# Page2.net
KiCad netlist of a schematic drawn in Altium Designer
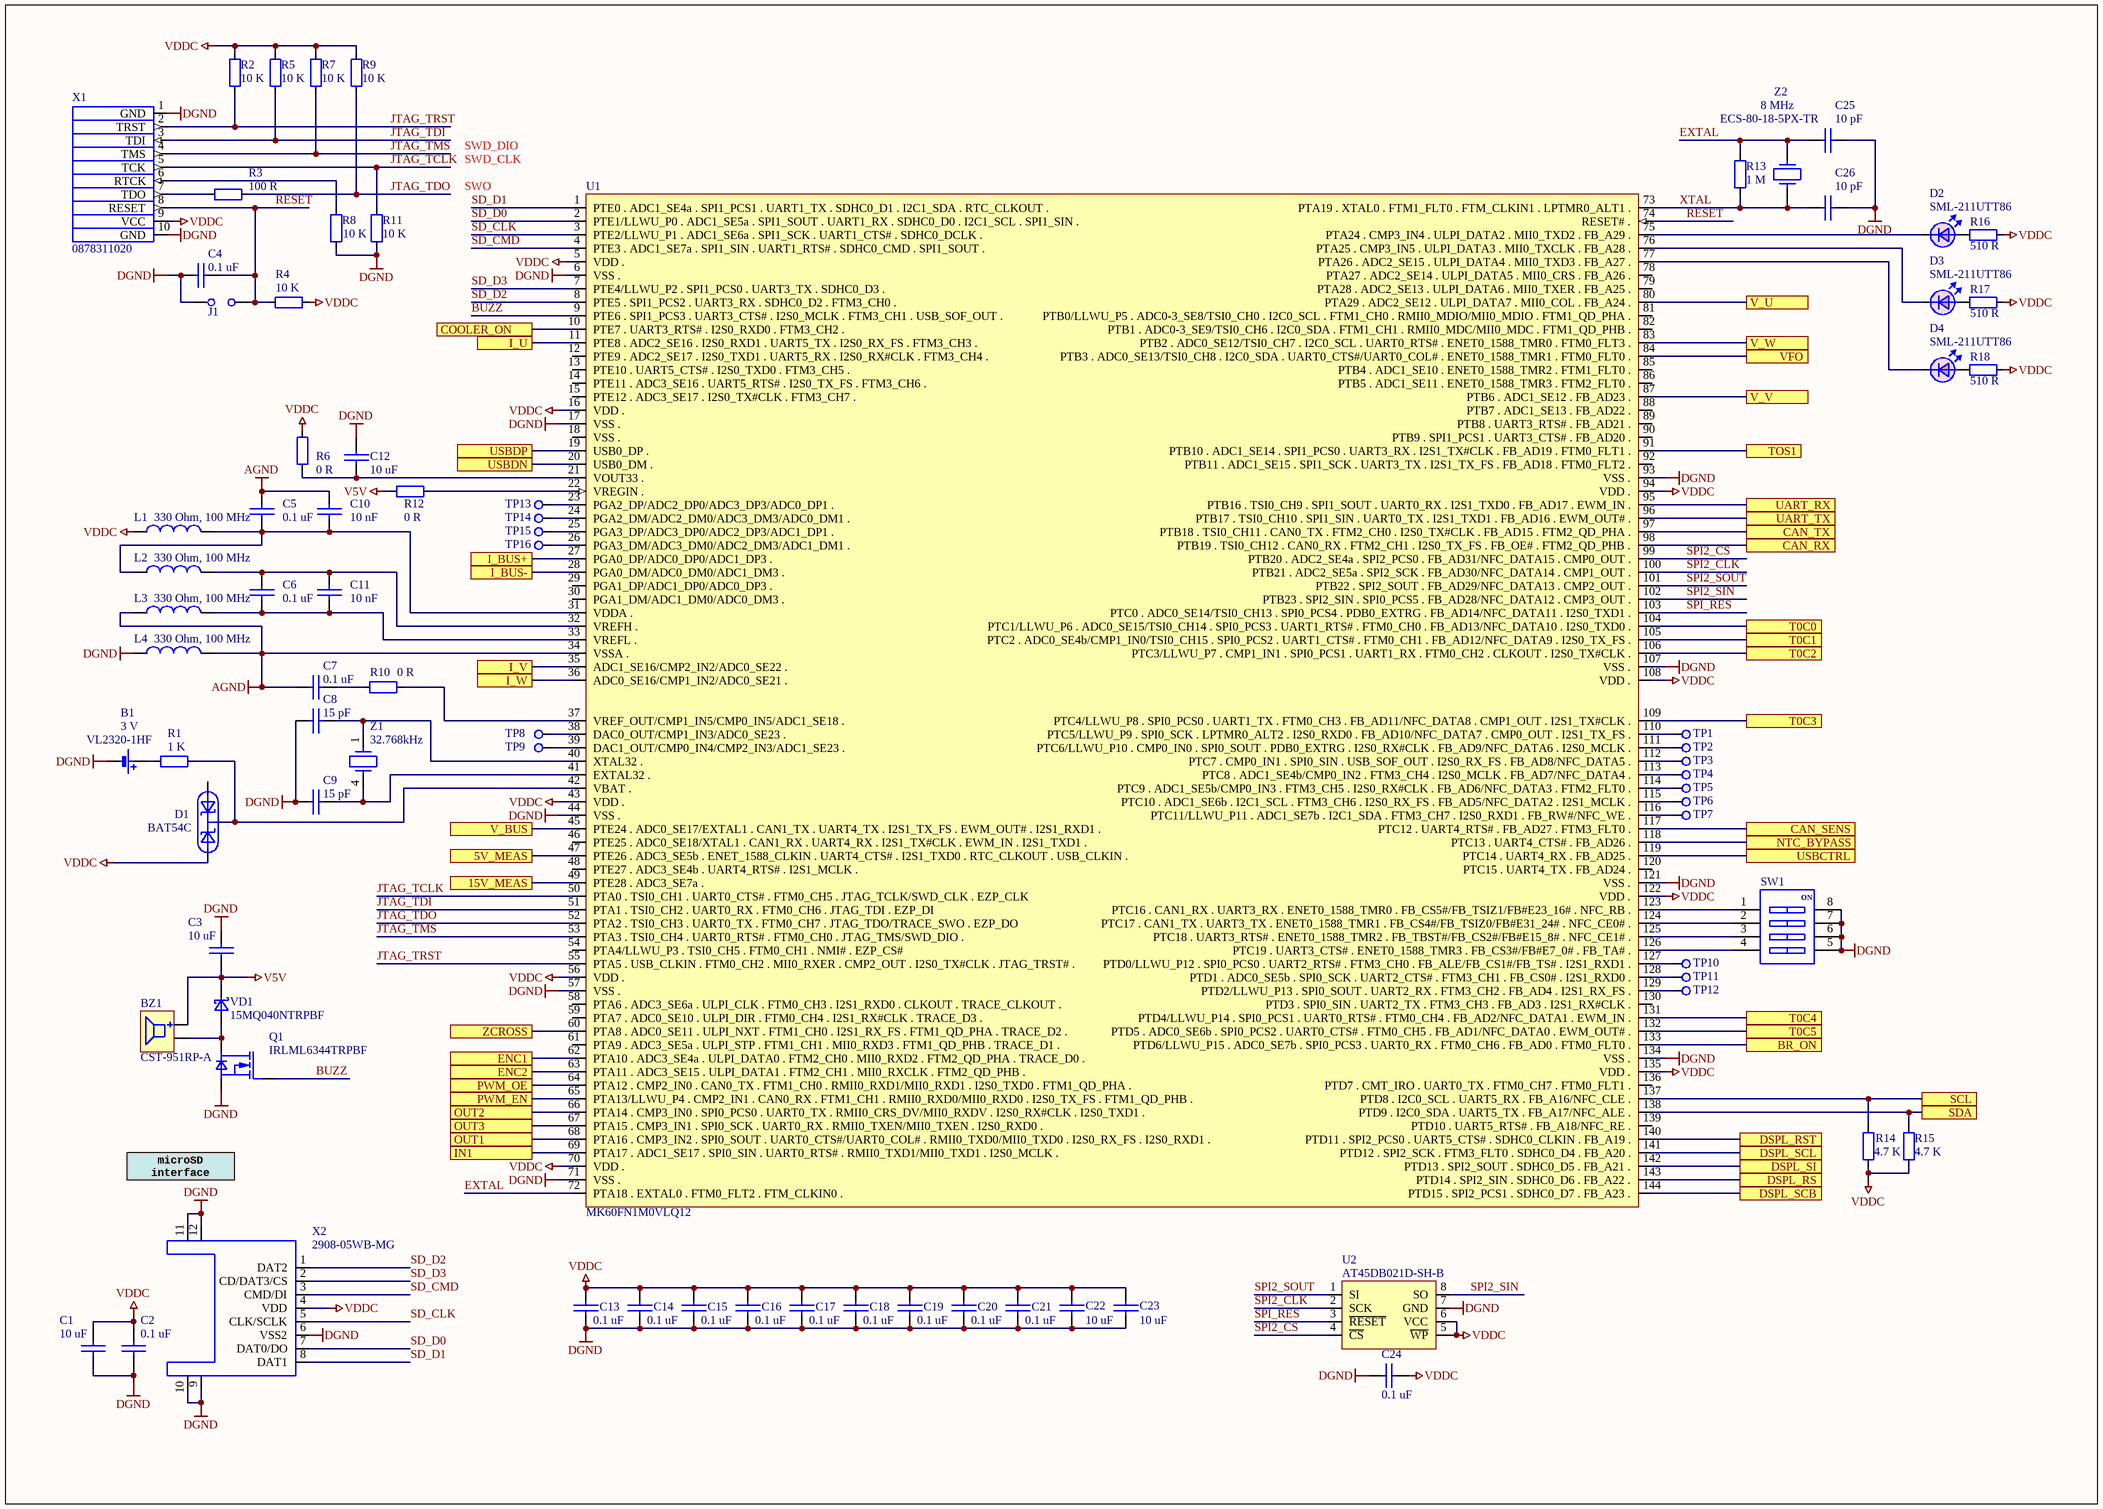
[diagram p0: Page2.SchDoc]

(export (version "E")
  (design (tool "Eeschema 10.0.6"))
  (components
    (comp (ref "B1")
      (value "VL2320-1HF")
      (footprint "SANYO ML2430")
      (description "Rechargeable Litium battery, Sanyo, 100 mAh, 3.1 V")
      (fields
        (field (name "PARTNUM") "P083-ND")
        (field (name "MANUFACTURER") "Panasonic - BSG")
        (field (name "ALTIUM_VALUE") "3 V")
      )
      (libsource (lib "*") (part "VL2320-1HF"))
    )
    (comp (ref "BZ1")
      (value "CST-951RP-A")
      (footprint "CST-951RP-A")
      (description "Buzzer CST-951AP, 4,5...5,5 V,  85 dB,   80 mA")
      (fields (field (name "MANUFACTURER") "CUI Inc") (field (name "PARTNUM") "102-1462-ND"))
      (libsource (lib "ea_Sound_devices") (part "CST-951RP-A"))
    )
    (comp (ref "C1")
      (value "10 uF")
      (footprint "2012[0805]")
      (description "10 uF, 16V, X5R, ±10%, 0805")
      (fields (field (name "MANUFACTURER") "TDK Corporation") (field (name "TOLERANCE") "±10%"))
      (libsource (lib "ea_Capacitors") (part "C2012X5R1C106K/0.85"))
    )
    (comp (ref "C2")
      (value "0.1 uF")
      (footprint "1608[0603]")
      (description "0.1 uF, 25V, 10% , X7R,  0603 SMD MLC Capacitor")
      (fields (field (name "TOLERANCE") "10%") (field (name "MANUFACTURER") "SAMSUNG"))
      (libsource (lib "ea_Capacitors") (part "CVNF100K0603-25"))
    )
    (comp (ref "C3")
      (value "10 uF")
      (footprint "2012[0805]")
      (description "10 uF, 16V, X5R, ±10%, 0805")
      (fields (field (name "MANUFACTURER") "TDK Corporation") (field (name "TOLERANCE") "±10%"))
      (libsource (lib "ea_Capacitors") (part "C2012X5R1C106K/0.85"))
    )
    (comp (ref "C4")
      (value "0.1 uF")
      (footprint "1608[0603]")
      (description "0.1 uF, 25V, 10% , X7R,  0603 SMD MLC Capacitor")
      (fields (field (name "TOLERANCE") "10%") (field (name "MANUFACTURER") "SAMSUNG"))
      (libsource (lib "ea_Capacitors") (part "CVNF100K0603-25"))
    )
    (comp (ref "C5")
      (value "0.1 uF")
      (footprint "1608[0603]")
      (description "0.1 uF, 25V, 10% , X7R,  0603 SMD MLC Capacitor")
      (fields (field (name "TOLERANCE") "10%") (field (name "MANUFACTURER") "SAMSUNG"))
      (libsource (lib "ea_Capacitors") (part "CVNF100K0603-25"))
    )
    (comp (ref "C6")
      (value "0.1 uF")
      (footprint "1608[0603]")
      (description "0.1 uF, 25V, 10% , X7R,  0603 SMD MLC Capacitor")
      (fields (field (name "TOLERANCE") "10%") (field (name "MANUFACTURER") "SAMSUNG"))
      (libsource (lib "ea_Capacitors") (part "CVNF100K0603-25"))
    )
    (comp (ref "C7")
      (value "0.1 uF")
      (footprint "1608[0603]")
      (description "0.1 uF, 25V, 10% , X7R,  0603 SMD MLC Capacitor")
      (fields (field (name "TOLERANCE") "10%") (field (name "MANUFACTURER") "SAMSUNG"))
      (libsource (lib "ea_Capacitors") (part "CVNF100K0603-25"))
    )
    (comp (ref "C8")
      (value "15 pF")
      (footprint "1608[0603]")
      (description "15 pF, 50V, 5%, NP0, 0603 SMD MLC Capacitor")
      (fields (field (name "MANUFACTURER") "YAGEO AMERICA CORPORATION") (field (name "TOLERANCE") "5%"))
      (libsource (lib "ea_Capacitors") (part "CCPF015K0603"))
    )
    (comp (ref "C9")
      (value "15 pF")
      (footprint "1608[0603]")
      (description "15 pF, 50V, 5%, NP0, 0603 SMD MLC Capacitor")
      (fields (field (name "MANUFACTURER") "YAGEO AMERICA CORPORATION") (field (name "TOLERANCE") "5%"))
      (libsource (lib "ea_Capacitors") (part "CCPF015K0603"))
    )
    (comp (ref "C10")
      (value "10 nF")
      (footprint "1608[0603]")
      (description "10 nF, 50V, 5%, X7R, 0603 SMD MLC Capacitor")
      (fields (field (name "TOLERANCE") "5%") (field (name "MANUFACTURER") "SAMSUNG"))
      (libsource (lib "ea_Capacitors") (part "CVNF010K0603"))
    )
    (comp (ref "C11")
      (value "10 nF")
      (footprint "1608[0603]")
      (description "10 nF, 50V, 5%, X7R, 0603 SMD MLC Capacitor")
      (fields (field (name "TOLERANCE") "5%") (field (name "MANUFACTURER") "SAMSUNG"))
      (libsource (lib "ea_Capacitors") (part "CVNF010K0603"))
    )
    (comp (ref "C12")
      (value "10 uF")
      (footprint "2012[0805]")
      (description "10 uF, 16V, X5R, ±10%, 0805")
      (fields (field (name "MANUFACTURER") "TDK Corporation") (field (name "TOLERANCE") "±10%"))
      (libsource (lib "ea_Capacitors") (part "C2012X5R1C106K/0.85"))
    )
    (comp (ref "C13")
      (value "0.1 uF")
      (footprint "1608[0603]")
      (description "0.1 uF, 25V, 10% , X7R,  0603 SMD MLC Capacitor")
      (fields (field (name "TOLERANCE") "10%") (field (name "MANUFACTURER") "SAMSUNG"))
      (libsource (lib "ea_Capacitors") (part "CVNF100K0603-25"))
    )
    (comp (ref "C14")
      (value "0.1 uF")
      (footprint "1608[0603]")
      (description "0.1 uF, 25V, 10% , X7R,  0603 SMD MLC Capacitor")
      (fields (field (name "TOLERANCE") "10%") (field (name "MANUFACTURER") "SAMSUNG"))
      (libsource (lib "ea_Capacitors") (part "CVNF100K0603-25"))
    )
    (comp (ref "C15")
      (value "0.1 uF")
      (footprint "1608[0603]")
      (description "0.1 uF, 25V, 10% , X7R,  0603 SMD MLC Capacitor")
      (fields (field (name "TOLERANCE") "10%") (field (name "MANUFACTURER") "SAMSUNG"))
      (libsource (lib "ea_Capacitors") (part "CVNF100K0603-25"))
    )
    (comp (ref "C16")
      (value "0.1 uF")
      (footprint "1608[0603]")
      (description "0.1 uF, 25V, 10% , X7R,  0603 SMD MLC Capacitor")
      (fields (field (name "TOLERANCE") "10%") (field (name "MANUFACTURER") "SAMSUNG"))
      (libsource (lib "ea_Capacitors") (part "CVNF100K0603-25"))
    )
    (comp (ref "C17")
      (value "0.1 uF")
      (footprint "1608[0603]")
      (description "0.1 uF, 25V, 10% , X7R,  0603 SMD MLC Capacitor")
      (fields (field (name "TOLERANCE") "10%") (field (name "MANUFACTURER") "SAMSUNG"))
      (libsource (lib "ea_Capacitors") (part "CVNF100K0603-25"))
    )
    (comp (ref "C18")
      (value "0.1 uF")
      (footprint "1608[0603]")
      (description "0.1 uF, 25V, 10% , X7R,  0603 SMD MLC Capacitor")
      (fields (field (name "TOLERANCE") "10%") (field (name "MANUFACTURER") "SAMSUNG"))
      (libsource (lib "ea_Capacitors") (part "CVNF100K0603-25"))
    )
    (comp (ref "C19")
      (value "0.1 uF")
      (footprint "1608[0603]")
      (description "0.1 uF, 25V, 10% , X7R,  0603 SMD MLC Capacitor")
      (fields (field (name "TOLERANCE") "10%") (field (name "MANUFACTURER") "SAMSUNG"))
      (libsource (lib "ea_Capacitors") (part "CVNF100K0603-25"))
    )
    (comp (ref "C20")
      (value "0.1 uF")
      (footprint "1608[0603]")
      (description "0.1 uF, 25V, 10% , X7R,  0603 SMD MLC Capacitor")
      (fields (field (name "TOLERANCE") "10%") (field (name "MANUFACTURER") "SAMSUNG"))
      (libsource (lib "ea_Capacitors") (part "CVNF100K0603-25"))
    )
    (comp (ref "C21")
      (value "0.1 uF")
      (footprint "1608[0603]")
      (description "0.1 uF, 25V, 10% , X7R,  0603 SMD MLC Capacitor")
      (fields (field (name "TOLERANCE") "10%") (field (name "MANUFACTURER") "SAMSUNG"))
      (libsource (lib "ea_Capacitors") (part "CVNF100K0603-25"))
    )
    (comp (ref "C22")
      (value "10 uF")
      (footprint "2012[0805]")
      (description "10 uF, 16V, X5R, ±10%, 0805")
      (fields (field (name "MANUFACTURER") "TDK Corporation") (field (name "TOLERANCE") "±10%"))
      (libsource (lib "ea_Capacitors") (part "C2012X5R1C106K/0.85"))
    )
    (comp (ref "C23")
      (value "10 uF")
      (footprint "2012[0805]")
      (description "10 uF, 16V, X5R, ±10%, 0805")
      (fields (field (name "MANUFACTURER") "TDK Corporation") (field (name "TOLERANCE") "±10%"))
      (libsource (lib "ea_Capacitors") (part "C2012X5R1C106K/0.85"))
    )
    (comp (ref "C24")
      (value "0.1 uF")
      (footprint "1608[0603]")
      (description "0.1 uF, 25V, 10% , X7R,  0603 SMD MLC Capacitor")
      (fields (field (name "TOLERANCE") "10%") (field (name "MANUFACTURER") "SAMSUNG"))
      (libsource (lib "ea_Capacitors") (part "CVNF100K0603-25"))
    )
    (comp (ref "C25")
      (value "10 pF")
      (footprint "1608[0603]")
      (description "10 pF, 50V, 5%, NP0, 0603 SMD MLC Capacitor")
      (fields (field (name "MANUFACTURER") "Kemet") (field (name "TOLERANCE") "5%"))
      (libsource (lib "ea_Capacitors") (part "CCPF010K0603"))
    )
    (comp (ref "C26")
      (value "10 pF")
      (footprint "1608[0603]")
      (description "10 pF, 50V, 5%, NP0, 0603 SMD MLC Capacitor")
      (fields (field (name "MANUFACTURER") "Kemet") (field (name "TOLERANCE") "5%"))
      (libsource (lib "ea_Capacitors") (part "CCPF010K0603"))
    )
    (comp (ref "D1")
      (value "BAT54C")
      (footprint "SOT23")
      (description "Schottky Diode, 30 V, 200 mA, common cathode")
      (fields
        (field (name "MANUFACTURER") "Fairchild Semiconductor")
        (field (name "PARTNUM") "BAT54CFSCT-ND")
      )
      (libsource (lib "ea_Diodes") (part "BAT54C"))
    )
    (comp (ref "D2")
      (value "SML-211UTT86")
      (footprint "0805 LED")
      (description "0805 red LED, hibright, 2 mA, 1.8V, 130°")
      (fields (field (name "MANUFACTURER") "Rohm") (field (name "PARTNUM") "511-1292-1-ND"))
      (libsource (lib "ea_Indicators") (part "SML-211UTT86"))
    )
    (comp (ref "D3")
      (value "SML-211UTT86")
      (footprint "0805 LED")
      (description "0805 red LED, hibright, 2 mA, 1.8V, 130°")
      (fields (field (name "MANUFACTURER") "Rohm") (field (name "PARTNUM") "511-1292-1-ND"))
      (libsource (lib "ea_Indicators") (part "SML-211UTT86"))
    )
    (comp (ref "D4")
      (value "SML-211UTT86")
      (footprint "0805 LED")
      (description "0805 red LED, hibright, 2 mA, 1.8V, 130°")
      (fields (field (name "MANUFACTURER") "Rohm") (field (name "PARTNUM") "511-1292-1-ND"))
      (libsource (lib "ea_Indicators") (part "SML-211UTT86"))
    )
    (comp (ref "J1")
      (value "PH1-02-TA-HT")
      (footprint "HDR1X2V")
      (description "2 Pos. 2.54 mm Single Row Through Hole Straight Pin Header")
      (fields (field (name "MANUFACTURER") "ADAM TECH"))
      (libsource (lib "ea_Commutation") (part "Jumper"))
    )
    (comp (ref "L1")
      (value "330 Ohm, 100 MHz")
      (footprint "0603")
      (description "Ferrite bead, 330 Ohm, 100 MHz,  1.5 A, 0.07 Ohm")
      (fields
        (field (name "MANUFACTURER") "Murata Electronics North America")
        (field (name "PARTNUM") "BLM18SG331TN1D")
      )
      (libsource (lib "*") (part "BLM18SG331TN1D"))
    )
    (comp (ref "L2")
      (value "330 Ohm, 100 MHz")
      (footprint "0603")
      (description "Ferrite bead, 330 Ohm, 100 MHz,  1.5 A, 0.07 Ohm")
      (fields
        (field (name "MANUFACTURER") "Murata Electronics North America")
        (field (name "PARTNUM") "BLM18SG331TN1D")
      )
      (libsource (lib "*") (part "BLM18SG331TN1D"))
    )
    (comp (ref "L3")
      (value "330 Ohm, 100 MHz")
      (footprint "0603")
      (description "Ferrite bead, 330 Ohm, 100 MHz,  1.5 A, 0.07 Ohm")
      (fields
        (field (name "MANUFACTURER") "Murata Electronics North America")
        (field (name "PARTNUM") "BLM18SG331TN1D")
      )
      (libsource (lib "*") (part "BLM18SG331TN1D"))
    )
    (comp (ref "L4")
      (value "330 Ohm, 100 MHz")
      (footprint "0603")
      (description "Ferrite bead, 330 Ohm, 100 MHz,  1.5 A, 0.07 Ohm")
      (fields
        (field (name "MANUFACTURER") "Murata Electronics North America")
        (field (name "PARTNUM") "BLM18SG331TN1D")
      )
      (libsource (lib "*") (part "BLM18SG331TN1D"))
    )
    (comp (ref "Q1")
      (value "IRLML6344TRPBF")
      (footprint "SOT23")
      (description "N-channel MOSFET, 30V, 5A, 0.030 Ohm 3.3 V, SOT-23")
      (fields
        (field (name "MANUFACTURER") "International Rectifier")
        (field (name "PARTNUM") "IRLML6344TRPBFCT-ND")
      )
      (libsource (lib "ea_MOSFET_&_drivers") (part "IRLML6344TRPBF"))
    )
    (comp (ref "R1")
      (value "1 K")
      (footprint "0603")
      (description "1 K, 1%, 0603, SMD Resistor, Taped")
      (fields (field (name "MANUFACTURER") "YAGEO AMERICA CORPORATION") (field (name "TOLERANCE") "1%"))
      (libsource (lib "ea_Resistors") (part "RL0603K001-1"))
    )
    (comp (ref "R2")
      (value "10 K")
      (footprint "0603")
      (description "10 K, 1%, 0603, SMD Resistor, Taped")
      (fields (field (name "MANUFACTURER") "PANASONIC") (field (name "TOLERANCE") "1%"))
      (libsource (lib "ea_Resistors") (part "RL0603K010-1"))
    )
    (comp (ref "R3")
      (value "100 R")
      (footprint "0603")
      (description "100 R, 1%, 0603, SMD Resistor, Taped")
      (fields (field (name "MANUFACTURER") "PANASONIC") (field (name "TOLERANCE") "1%"))
      (libsource (lib "ea_Resistors") (part "RL0603E100-1"))
    )
    (comp (ref "R4")
      (value "10 K")
      (footprint "0603")
      (description "10 K, 1%, 0603, SMD Resistor, Taped")
      (fields (field (name "MANUFACTURER") "PANASONIC") (field (name "TOLERANCE") "1%"))
      (libsource (lib "") (part "RL0603K010-1_1"))
    )
    (comp (ref "R5")
      (value "10 K")
      (footprint "0603")
      (description "10 K, 1%, 0603, SMD Resistor, Taped")
      (fields (field (name "MANUFACTURER") "PANASONIC") (field (name "TOLERANCE") "1%"))
      (libsource (lib "ea_Resistors") (part "RL0603K010-1"))
    )
    (comp (ref "R6")
      (value "0 R")
      (footprint "0603")
      (description "0 R, 5%, 0603, SMD Resistor, Taped")
      (fields (field (name "MANUFACTURER") "YAGEO AMERICA CORPORATION") (field (name "TOLERANCE") "5%"))
      (libsource (lib "") (part "RL0603E000_1"))
    )
    (comp (ref "R7")
      (value "10 K")
      (footprint "0603")
      (description "10 K, 1%, 0603, SMD Resistor, Taped")
      (fields (field (name "MANUFACTURER") "PANASONIC") (field (name "TOLERANCE") "1%"))
      (libsource (lib "ea_Resistors") (part "RL0603K010-1"))
    )
    (comp (ref "R8")
      (value "10 K")
      (footprint "0603")
      (description "10 K, 1%, 0603, SMD Resistor, Taped")
      (fields (field (name "MANUFACTURER") "PANASONIC") (field (name "TOLERANCE") "1%"))
      (libsource (lib "ea_Resistors") (part "RL0603K010-1"))
    )
    (comp (ref "R9")
      (value "10 K")
      (footprint "0603")
      (description "10 K, 1%, 0603, SMD Resistor, Taped")
      (fields (field (name "MANUFACTURER") "PANASONIC") (field (name "TOLERANCE") "1%"))
      (libsource (lib "ea_Resistors") (part "RL0603K010-1"))
    )
    (comp (ref "R10")
      (value "0 R")
      (footprint "0603")
      (description "0 R, 5%, 0603, SMD Resistor, Taped")
      (fields (field (name "MANUFACTURER") "YAGEO AMERICA CORPORATION") (field (name "TOLERANCE") "5%"))
      (libsource (lib "") (part "RL0603E000_2"))
    )
    (comp (ref "R11")
      (value "10 K")
      (footprint "0603")
      (description "10 K, 1%, 0603, SMD Resistor, Taped")
      (fields (field (name "MANUFACTURER") "PANASONIC") (field (name "TOLERANCE") "1%"))
      (libsource (lib "ea_Resistors") (part "RL0603K010-1"))
    )
    (comp (ref "R12")
      (value "0 R")
      (footprint "0603")
      (description "0 R, 5%, 0603, SMD Resistor, Taped")
      (fields (field (name "MANUFACTURER") "YAGEO AMERICA CORPORATION") (field (name "TOLERANCE") "5%"))
      (libsource (lib "ea_Resistors") (part "RL0603E000"))
    )
    (comp (ref "R13")
      (value "1 M")
      (footprint "0603")
      (description "1 M, 1%, 0603, SMD Resistor, Taped")
      (fields (field (name "MANUFACTURER") "YAGEO AMERICA CORPORATION") (field (name "TOLERANCE") "1%"))
      (libsource (lib "ea_Resistors") (part "RC0603FR-071ML"))
    )
    (comp (ref "R14")
      (value "4.7 K")
      (footprint "0603")
      (description "4.7 K, 1%, 0603, SMD Resistor, Taped")
      (fields (field (name "MANUFACTURER") "YAGEO AMERICA CORPORATION") (field (name "TOLERANCE") "1%"))
      (libsource (lib "ea_Resistors") (part "RL0603K004.7-1_1"))
    )
    (comp (ref "R15")
      (value "4.7 K")
      (footprint "0603")
      (description "4.7 K, 1%, 0603, SMD Resistor, Taped")
      (fields (field (name "MANUFACTURER") "YAGEO AMERICA CORPORATION") (field (name "TOLERANCE") "1%"))
      (libsource (lib "ea_Resistors") (part "RL0603K004.7-1_1"))
    )
    (comp (ref "R16")
      (value "510 R")
      (footprint "0603")
      (description "510 R, 1%, 0603, SMD Resistor, Taped")
      (fields (field (name "MANUFACTURER") "Vishay") (field (name "TOLERANCE") "1%"))
      (libsource (lib "ea_Resistors") (part "RL0603E510-1"))
    )
    (comp (ref "R17")
      (value "510 R")
      (footprint "0603")
      (description "510 R, 1%, 0603, SMD Resistor, Taped")
      (fields (field (name "MANUFACTURER") "Vishay") (field (name "TOLERANCE") "1%"))
      (libsource (lib "ea_Resistors") (part "RL0603E510-1"))
    )
    (comp (ref "R18")
      (value "510 R")
      (footprint "0603")
      (description "510 R, 1%, 0603, SMD Resistor, Taped")
      (fields (field (name "MANUFACTURER") "Vishay") (field (name "TOLERANCE") "1%"))
      (libsource (lib "ea_Resistors") (part "RL0603E510-1"))
    )
    (comp (ref "SW1")
      (value "MCDHN-04F-T-V")
      (footprint "MCDHN-04F-T-V")
      (description "SWITCH, DIP, SMD, 4 WAY, 1.27mm")
      (fields (field (name "MANUFACTURER") "MULTICOMP") (field (name "PARTNUM") "1605479"))
      (libsource (lib "ea_Commutation") (part "MCDHN-04F-T-V"))
    )
    (comp (ref "TP1")
      (value "TP 0.5 mm")
      (footprint "Test Point 0.5 mm")
      (libsource (lib "ea_Mechanical") (part "TP 0.5 mm"))
    )
    (comp (ref "TP2")
      (value "TP 0.5 mm")
      (footprint "Test Point 0.5 mm")
      (libsource (lib "ea_Mechanical") (part "TP 0.5 mm"))
    )
    (comp (ref "TP3")
      (value "TP 0.5 mm")
      (footprint "Test Point 0.5 mm")
      (libsource (lib "ea_Mechanical") (part "TP 0.5 mm"))
    )
    (comp (ref "TP4")
      (value "TP 0.5 mm")
      (footprint "Test Point 0.5 mm")
      (libsource (lib "ea_Mechanical") (part "TP 0.5 mm"))
    )
    (comp (ref "TP5")
      (value "TP 0.5 mm")
      (footprint "Test Point 0.5 mm")
      (libsource (lib "ea_Mechanical") (part "TP 0.5 mm"))
    )
    (comp (ref "TP6")
      (value "TP 0.5 mm")
      (footprint "Test Point 0.5 mm")
      (libsource (lib "ea_Mechanical") (part "TP 0.5 mm"))
    )
    (comp (ref "TP7")
      (value "TP 0.5 mm")
      (footprint "Test Point 0.5 mm")
      (libsource (lib "ea_Mechanical") (part "TP 0.5 mm"))
    )
    (comp (ref "TP8")
      (value "TP 0.5 mm")
      (footprint "Test Point 0.5 mm")
      (libsource (lib "ea_Mechanical") (part "TP 0.5 mm"))
    )
    (comp (ref "TP9")
      (value "TP 0.5 mm")
      (footprint "Test Point 0.5 mm")
      (libsource (lib "ea_Mechanical") (part "TP 0.5 mm"))
    )
    (comp (ref "TP10")
      (value "TP 0.5 mm")
      (footprint "Test Point 0.5 mm")
      (libsource (lib "ea_Mechanical") (part "TP 0.5 mm"))
    )
    (comp (ref "TP11")
      (value "TP 0.5 mm")
      (footprint "Test Point 0.5 mm")
      (libsource (lib "ea_Mechanical") (part "TP 0.5 mm"))
    )
    (comp (ref "TP12")
      (value "TP 0.5 mm")
      (footprint "Test Point 0.5 mm")
      (libsource (lib "ea_Mechanical") (part "TP 0.5 mm"))
    )
    (comp (ref "TP13")
      (value "TP 0.5 mm")
      (footprint "Test Point 0.5 mm")
      (libsource (lib "ea_Mechanical") (part "TP 0.5 mm"))
    )
    (comp (ref "TP14")
      (value "TP 0.5 mm")
      (footprint "Test Point 0.5 mm")
      (libsource (lib "ea_Mechanical") (part "TP 0.5 mm"))
    )
    (comp (ref "TP15")
      (value "TP 0.5 mm")
      (footprint "Test Point 0.5 mm")
      (libsource (lib "ea_Mechanical") (part "TP 0.5 mm"))
    )
    (comp (ref "TP16")
      (value "TP 0.5 mm")
      (footprint "Test Point 0.5 mm")
      (libsource (lib "ea_Mechanical") (part "TP 0.5 mm"))
    )
    (comp (ref "U1")
      (value "MK60FN1M0VLQ12")
      (footprint "ea_TQFP:LQFP144")
      (description "MK60 Series 32 Bit 1 MB Flash 128 KB Ram 120 Mhz Microcontroller - LQFP-144")
      (fields (field (name "MANUFACTURER") "Freescale"))
      (libsource (lib "ea_IC_CPU") (part "MK60FN1M0VLQ12"))
    )
    (comp (ref "U2")
      (value "AT45DB021D-SH-B")
      (footprint "SO-8  wide")
      (description "IC DATAFLASH 1MBIT 2.7 V ~ 3.6 V 8-SOIC")
      (fields (field (name "MANUFACTURER") "Adesto Technologies") (field (name "PARTNUM") "1265-1033-1-ND"))
      (libsource (lib "ea_IC_NOR_NAND_FLASH") (part "AT45DB011D-SH-T"))
    )
    (comp (ref "VD1")
      (value "15MQ040NTRPBF")
      (footprint "SMA")
      (description "Schottky Power Rectifier 3A, 40V, SMA")
      (fields (field (name "MANUFACTURER") "VISHAY"))
      (libsource (lib "ea_Diodes") (part "15MQ040N"))
    )
    (comp (ref "X1")
      (value "0878311020")
      (footprint "878311020 MGRID WALL HDR")
      (description "CONN HEADER 10POS 2MM VERT GOLD")
      (fields (field (name "MANUFACTURER") "Molex Inc") (field (name "PARTNUM") "WM18560-ND"))
      (libsource (lib "ea_Connectors") (part "87831-1020"))
    )
    (comp (ref "X2")
      (value "2908-05WB-MG")
      (footprint "2908-05WB-MG")
      (description "microSD cadr holder")
      (fields
        (field (name "MANUFACTURER") "Amphenol Commercial Products")
        (field (name "PARTNUM") "101-00660-68-6-1-ND")
      )
      (libsource (lib "ea_CARD_holders") (part "2908-05WB-MG"))
    )
    (comp (ref "Z1")
      (value "32.768kHz")
      (footprint "CM200S")
      (description "Crystal 32.768 kHz ±20 ppm 6 pF -40 to +85 °C SMT Tuning Fork Crystal")
      (fields
        (field (name "MANUFACTURER") "CITIZEN FINETECH MIYOTA")
        (field (name "PARTNUM") "CM200C32768DZBT")
      )
      (libsource (lib "*") (part "MC306-32,768"))
    )
    (comp (ref "Z2")
      (value "ECS-80-18-5PX-TR")
      (footprint "Quartz Crystal SMU4")
      (fields
        (field (name "MANUFACTURER") "ECS Inc.")
        (field (name "ALTIUM_VALUE") "8 MHz")
        (field (name "PARTNUM") "XC1271CT-ND")
      )
      (libsource (lib "*") (part "ECS-80-18-5PX-TR"))
    )
  )
  (nets
    (net (code "1") (name "/5V_MEAS") (class "Default")
      (node (ref "U1") (pin "47") (pinfunction "PTE26_._ADC3_SE5b_._ENET_1588_CLKIN_._UART4_CTS#_._I2S1_TXD0_._RTC_CLKOUT_._USB_CLKIN_._47") (pintype "bidirectional"))
    )
    (net (code "2") (name "/15V_MEAS") (class "Default")
      (node (ref "U1") (pin "49") (pinfunction "PTE28_._ADC3_SE7a_._49") (pintype "bidirectional"))
    )
    (net (code "3") (name "/BR_ON") (class "Default")
      (node (ref "U1") (pin "133") (pinfunction "PTD6/LLWU_P15_._ADC0_SE7b_._SPI0_PCS3_._UART0_RX_._FTM0_CH6_._FB_AD0_._FTM0_FLT0_._133") (pintype "bidirectional"))
    )
    (net (code "4") (name "/BUZZ") (class "Default")
      (node (ref "Q1") (pin "1") (pinfunction "G_1") (pintype "passive"))
      (node (ref "U1") (pin "9") (pinfunction "PTE6_._SPI1_PCS3_._UART3_CTS#_._I2S0_MCLK_._FTM3_CH1_._USB_SOF_OUT_._9") (pintype "bidirectional"))
    )
    (net (code "5") (name "/CAN_RX") (class "Default")
      (node (ref "U1") (pin "98") (pinfunction "PTB19_._TSI0_CH12_._CAN0_RX_._FTM2_CH1_._I2S0_TX_FS_._FB_OE#_._FTM2_QD_PHB_._98") (pintype "bidirectional"))
    )
    (net (code "6") (name "/CAN_SENS") (class "Default")
      (node (ref "U1") (pin "117") (pinfunction "PTC12_._UART4_RTS#_._FB_AD27_._FTM3_FLT0_._117") (pintype "bidirectional"))
    )
    (net (code "7") (name "/CAN_TX") (class "Default")
      (node (ref "U1") (pin "97") (pinfunction "PTB18_._TSI0_CH11_._CAN0_TX_._FTM2_CH0_._I2S0_TX#CLK_._FB_AD15_._FTM2_QD_PHA_._97") (pintype "bidirectional"))
    )
    (net (code "8") (name "/COOLER_ON") (class "Default")
      (node (ref "U1") (pin "10") (pinfunction "PTE7_._UART3_RTS#_._I2S0_RXD0_._FTM3_CH2_._10") (pintype "bidirectional"))
    )
    (net (code "9") (name "/DSPL_RS") (class "Default")
      (node (ref "U1") (pin "143") (pinfunction "PTD14_._SPI2_SIN_._SDHC0_D6_._FB_A22_._143") (pintype "bidirectional"))
    )
    (net (code "10") (name "/DSPL_RST") (class "Default")
      (node (ref "U1") (pin "140") (pinfunction "PTD11_._SPI2_PCS0_._UART5_CTS#_._SDHC0_CLKIN_._FB_A19_._140") (pintype "bidirectional"))
    )
    (net (code "11") (name "/DSPL_SCB") (class "Default")
      (node (ref "U1") (pin "144") (pinfunction "PTD15_._SPI2_PCS1_._SDHC0_D7_._FB_A23_._144") (pintype "bidirectional"))
    )
    (net (code "12") (name "/DSPL_SCL") (class "Default")
      (node (ref "U1") (pin "141") (pinfunction "PTD12_._SPI2_SCK_._FTM3_FLT0_._SDHC0_D4_._FB_A20_._141") (pintype "bidirectional"))
    )
    (net (code "13") (name "/DSPL_SI") (class "Default")
      (node (ref "U1") (pin "142") (pinfunction "PTD13_._SPI2_SOUT_._SDHC0_D5_._FB_A21_._142") (pintype "bidirectional"))
    )
    (net (code "14") (name "/ENC1") (class "Default")
      (node (ref "U1") (pin "62") (pinfunction "PTA10_._ADC3_SE4a_._ULPI_DATA0_._FTM2_CH0_._MII0_RXD2_._FTM2_QD_PHA_._TRACE_D0_._62") (pintype "bidirectional"))
    )
    (net (code "15") (name "/ENC2") (class "Default")
      (node (ref "U1") (pin "63") (pinfunction "PTA11_._ADC3_SE15_._ULPI_DATA1_._FTM2_CH1_._MII0_RXCLK_._FTM2_QD_PHB_._63") (pintype "bidirectional"))
    )
    (net (code "16") (name "/EXTAL") (class "Default")
      (node (ref "C25") (pin "1") (pinfunction "1_1") (pintype "passive"))
      (node (ref "R13") (pin "2") (pinfunction "2_2") (pintype "passive"))
      (node (ref "U1") (pin "72") (pinfunction "PTA18_._EXTAL0_._FTM0_FLT2_._FTM_CLKIN0_._72") (pintype "bidirectional"))
      (node (ref "Z2") (pin "2") (pinfunction "2_2") (pintype "passive"))
    )
    (net (code "17") (name "/IN1") (class "Default")
      (node (ref "U1") (pin "69") (pinfunction "PTA17_._ADC1_SE17_._SPI0_SIN_._UART0_RTS#_._RMII0_TXD1/MII0_TXD1_._I2S0_MCLK_._69") (pintype "bidirectional"))
    )
    (net (code "18") (name "/I_BUS+") (class "Default")
      (node (ref "U1") (pin "27") (pinfunction "PGA0_DP/ADC0_DP0/ADC1_DP3_._27") (pintype "bidirectional"))
    )
    (net (code "19") (name "/I_BUS-") (class "Default")
      (node (ref "U1") (pin "28") (pinfunction "PGA0_DM/ADC0_DM0/ADC1_DM3_._28") (pintype "bidirectional"))
    )
    (net (code "20") (name "/I_U") (class "Default")
      (node (ref "U1") (pin "11") (pinfunction "PTE8_._ADC2_SE16_._I2S0_RXD1_._UART5_TX_._I2S0_RX_FS_._FTM3_CH3_._11") (pintype "bidirectional"))
    )
    (net (code "21") (name "/I_V") (class "Default")
      (node (ref "U1") (pin "35") (pinfunction "ADC1_SE16/CMP2_IN2/ADC0_SE22_._35") (pintype "bidirectional"))
    )
    (net (code "22") (name "/I_W") (class "Default")
      (node (ref "U1") (pin "36") (pinfunction "ADC0_SE16/CMP1_IN2/ADC0_SE21_._36") (pintype "bidirectional"))
    )
    (net (code "23") (name "/JTAG_TCLK") (class "Default")
      (node (ref "R11") (pin "1") (pinfunction "1_1") (pintype "passive"))
      (node (ref "U1") (pin "50") (pinfunction "PTA0_._TSI0_CH1_._UART0_CTS#_._FTM0_CH5_._JTAG_TCLK/SWD_CLK_._EZP_CLK_50") (pintype "bidirectional"))
      (node (ref "X1") (pin "5") (pinfunction "TCK_5") (pintype "output"))
    )
    (net (code "24") (name "/JTAG_TDI") (class "Default")
      (node (ref "R5") (pin "2") (pinfunction "2_2") (pintype "passive"))
      (node (ref "U1") (pin "51") (pinfunction "PTA1_._TSI0_CH2_._UART0_RX_._FTM0_CH6_._JTAG_TDI_._EZP_DI_51") (pintype "bidirectional"))
      (node (ref "X1") (pin "3") (pinfunction "TDI_3") (pintype "input"))
    )
    (net (code "25") (name "/JTAG_TDO") (class "Default")
      (node (ref "R3") (pin "1") (pinfunction "1_1") (pintype "passive"))
      (node (ref "R9") (pin "2") (pinfunction "2_2") (pintype "passive"))
      (node (ref "U1") (pin "52") (pinfunction "PTA2_._TSI0_CH3_._UART0_TX_._FTM0_CH7_._JTAG_TDO/TRACE_SWO_._EZP_DO_52") (pintype "bidirectional"))
    )
    (net (code "26") (name "/JTAG_TMS") (class "Default")
      (node (ref "R7") (pin "2") (pinfunction "2_2") (pintype "passive"))
      (node (ref "U1") (pin "53") (pinfunction "PTA3_._TSI0_CH4_._UART0_RTS#_._FTM0_CH0_._JTAG_TMS/SWD_DIO_._53") (pintype "bidirectional"))
      (node (ref "X1") (pin "4") (pinfunction "TMS_4") (pintype "output"))
    )
    (net (code "27") (name "/JTAG_TRST") (class "Default")
      (node (ref "R2") (pin "2") (pinfunction "2_2") (pintype "passive"))
      (node (ref "U1") (pin "55") (pinfunction "PTA5_._USB_CLKIN_._FTM0_CH2_._MII0_RXER_._CMP2_OUT_._I2S0_TX#CLK_._JTAG_TRST#_._55") (pintype "bidirectional"))
      (node (ref "X1") (pin "2") (pinfunction "TRST_2") (pintype "output"))
    )
    (net (code "28") (name "/NTC_BYPASS") (class "Default")
      (node (ref "U1") (pin "118") (pinfunction "PTC13_._UART4_CTS#_._FB_AD26_._118") (pintype "bidirectional"))
    )
    (net (code "29") (name "/OUT1") (class "Default")
      (node (ref "U1") (pin "68") (pinfunction "PTA16_._CMP3_IN2_._SPI0_SOUT_._UART0_CTS#/UART0_COL#_._RMII0_TXD0/MII0_TXD0_._I2S0_RX_FS_._I2S0_RXD1_._68") (pintype "bidirectional"))
    )
    (net (code "30") (name "/OUT2") (class "Default")
      (node (ref "U1") (pin "66") (pinfunction "PTA14_._CMP3_IN0_._SPI0_PCS0_._UART0_TX_._RMII0_CRS_DV/MII0_RXDV_._I2S0_RX#CLK_._I2S0_TXD1_._66") (pintype "bidirectional"))
    )
    (net (code "31") (name "/OUT3") (class "Default")
      (node (ref "U1") (pin "67") (pinfunction "PTA15_._CMP3_IN1_._SPI0_SCK_._UART0_RX_._RMII0_TXEN/MII0_TXEN_._I2S0_RXD0_._67") (pintype "bidirectional"))
    )
    (net (code "32") (name "/PWM_EN") (class "Default")
      (node (ref "U1") (pin "65") (pinfunction "PTA13/LLWU_P4_._CMP2_IN1_._CAN0_RX_._FTM1_CH1_._RMII0_RXD0/MII0_RXD0_._I2S0_TX_FS_._FTM1_QD_PHB_._65") (pintype "bidirectional"))
    )
    (net (code "33") (name "/PWM_OE") (class "Default")
      (node (ref "U1") (pin "64") (pinfunction "PTA12_._CMP2_IN0_._CAN0_TX_._FTM1_CH0_._RMII0_RXD1/MII0_RXD1_._I2S0_TXD0_._FTM1_QD_PHA_._64") (pintype "bidirectional"))
    )
    (net (code "34") (name "/RESET") (class "Default")
      (node (ref "C4") (pin "1") (pinfunction "1_1") (pintype "passive"))
      (node (ref "J1") (pin "1") (pinfunction "1_1") (pintype "passive"))
      (node (ref "R4") (pin "2") (pinfunction "2_2") (pintype "passive"))
      (node (ref "U1") (pin "74") (pinfunction "RESET#_._74") (pintype "input"))
      (node (ref "X1") (pin "8") (pinfunction "RESET_8") (pintype "output"))
    )
    (net (code "35") (name "/SCL") (class "Default")
      (node (ref "R14") (pin "2") (pinfunction "2_2") (pintype "passive"))
      (node (ref "U1") (pin "137") (pinfunction "PTD8_._I2C0_SCL_._UART5_RX_._FB_A16/NFC_CLE_._137") (pintype "bidirectional"))
    )
    (net (code "36") (name "/SDA") (class "Default")
      (node (ref "R15") (pin "2") (pinfunction "2_2") (pintype "passive"))
      (node (ref "U1") (pin "138") (pinfunction "PTD9_._I2C0_SDA_._UART5_TX_._FB_A17/NFC_ALE_._138") (pintype "bidirectional"))
    )
    (net (code "37") (name "/SD_CLK") (class "Default")
      (node (ref "U1") (pin "3") (pinfunction "PTE2/LLWU_P1_._ADC1_SE6a_._SPI1_SCK_._UART1_CTS#_._SDHC0_DCLK_._3") (pintype "bidirectional"))
      (node (ref "X2") (pin "5") (pinfunction "CLK/SCLK_5") (pintype "passive"))
    )
    (net (code "38") (name "/SD_CMD") (class "Default")
      (node (ref "U1") (pin "4") (pinfunction "PTE3_._ADC1_SE7a_._SPI1_SIN_._UART1_RTS#_._SDHC0_CMD_._SPI1_SOUT_._4") (pintype "bidirectional"))
      (node (ref "X2") (pin "3") (pinfunction "CMD/DI_3") (pintype "passive"))
    )
    (net (code "39") (name "/SD_D0") (class "Default")
      (node (ref "U1") (pin "2") (pinfunction "PTE1/LLWU_P0_._ADC1_SE5a_._SPI1_SOUT_._UART1_RX_._SDHC0_D0_._I2C1_SCL_._SPI1_SIN_._2") (pintype "bidirectional"))
      (node (ref "X2") (pin "7") (pinfunction "DAT0/DO_7") (pintype "passive"))
    )
    (net (code "40") (name "/SD_D1") (class "Default")
      (node (ref "U1") (pin "1") (pinfunction "PTE0_._ADC1_SE4a_._SPI1_PCS1_._UART1_TX_._SDHC0_D1_._I2C1_SDA_._RTC_CLKOUT_._1") (pintype "bidirectional"))
      (node (ref "X2") (pin "8") (pinfunction "DAT1_8") (pintype "passive"))
    )
    (net (code "41") (name "/SD_D2") (class "Default")
      (node (ref "U1") (pin "8") (pinfunction "PTE5_._SPI1_PCS2_._UART3_RX_._SDHC0_D2_._FTM3_CH0_._8") (pintype "bidirectional"))
      (node (ref "X2") (pin "1") (pinfunction "DAT2_1") (pintype "passive"))
    )
    (net (code "42") (name "/SD_D3") (class "Default")
      (node (ref "U1") (pin "7") (pinfunction "PTE4/LLWU_P2_._SPI1_PCS0_._UART3_TX_._SDHC0_D3_._7") (pintype "bidirectional"))
      (node (ref "X2") (pin "2") (pinfunction "CD/DAT3/CS_2") (pintype "passive"))
    )
    (net (code "43") (name "/SPI2_CLK") (class "Default")
      (node (ref "U1") (pin "100") (pinfunction "PTB21_._ADC2_SE5a_._SPI2_SCK_._FB_AD30/NFC_DATA14_._CMP1_OUT_._100") (pintype "bidirectional"))
      (node (ref "U2") (pin "2") (pinfunction "SCK_2") (pintype "passive"))
    )
    (net (code "44") (name "/SPI2_CS") (class "Default")
      (node (ref "U1") (pin "99") (pinfunction "PTB20_._ADC2_SE4a_._SPI2_PCS0_._FB_AD31/NFC_DATA15_._CMP0_OUT_._99") (pintype "bidirectional"))
      (node (ref "U2") (pin "4") (pinfunction "~{CS}_4") (pintype "passive"))
    )
    (net (code "45") (name "/SPI2_SIN") (class "Default")
      (node (ref "U1") (pin "102") (pinfunction "PTB23_._SPI2_SIN_._SPI0_PCS5_._FB_AD28/NFC_DATA12_._CMP3_OUT_._102") (pintype "bidirectional"))
      (node (ref "U2") (pin "8") (pinfunction "SO_8") (pintype "passive"))
    )
    (net (code "46") (name "/SPI2_SOUT") (class "Default")
      (node (ref "U1") (pin "101") (pinfunction "PTB22_._SPI2_SOUT_._FB_AD29/NFC_DATA13_._CMP2_OUT_._101") (pintype "bidirectional"))
      (node (ref "U2") (pin "1") (pinfunction "SI_1") (pintype "passive"))
    )
    (net (code "47") (name "/SPI_RES") (class "Default")
      (node (ref "U1") (pin "103") (pinfunction "PTC0_._ADC0_SE14/TSI0_CH13_._SPI0_PCS4_._PDB0_EXTRG_._FB_AD14/NFC_DATA11_._I2S0_TXD1_._103") (pintype "bidirectional"))
      (node (ref "U2") (pin "3") (pinfunction "~{RESET}_3") (pintype "passive"))
    )
    (net (code "48") (name "/T0C0") (class "Default")
      (node (ref "U1") (pin "104") (pinfunction "PTC1/LLWU_P6_._ADC0_SE15/TSI0_CH14_._SPI0_PCS3_._UART1_RTS#_._FTM0_CH0_._FB_AD13/NFC_DATA10_._I2S0_TXD0_._104") (pintype "bidirectional"))
    )
    (net (code "49") (name "/T0C1") (class "Default")
      (node (ref "U1") (pin "105") (pinfunction "PTC2_._ADC0_SE4b/CMP1_IN0/TSI0_CH15_._SPI0_PCS2_._UART1_CTS#_._FTM0_CH1_._FB_AD12/NFC_DATA9_._I2S0_TX_FS_._105") (pintype "bidirectional"))
    )
    (net (code "50") (name "/T0C2") (class "Default")
      (node (ref "U1") (pin "106") (pinfunction "PTC3/LLWU_P7_._CMP1_IN1_._SPI0_PCS1_._UART1_RX_._FTM0_CH2_._CLKOUT_._I2S0_TX#CLK_._106") (pintype "bidirectional"))
    )
    (net (code "51") (name "/T0C3") (class "Default")
      (node (ref "U1") (pin "109") (pinfunction "PTC4/LLWU_P8_._SPI0_PCS0_._UART1_TX_._FTM0_CH3_._FB_AD11/NFC_DATA8_._CMP1_OUT_._I2S1_TX#CLK_._109") (pintype "bidirectional"))
    )
    (net (code "52") (name "/T0C4") (class "Default")
      (node (ref "U1") (pin "131") (pinfunction "PTD4/LLWU_P14_._SPI0_PCS1_._UART0_RTS#_._FTM0_CH4_._FB_AD2/NFC_DATA1_._EWM_IN_._131") (pintype "bidirectional"))
    )
    (net (code "53") (name "/T0C5") (class "Default")
      (node (ref "U1") (pin "132") (pinfunction "PTD5_._ADC0_SE6b_._SPI0_PCS2_._UART0_CTS#_._FTM0_CH5_._FB_AD1/NFC_DATA0_._EWM_OUT#_._132") (pintype "bidirectional"))
    )
    (net (code "54") (name "/TOS1") (class "Default")
      (node (ref "U1") (pin "91") (pinfunction "PTB10_._ADC1_SE14_._SPI1_PCS0_._UART3_RX_._I2S1_TX#CLK_._FB_AD19_._FTM0_FLT1_._91") (pintype "bidirectional"))
    )
    (net (code "55") (name "/UART_RX") (class "Default")
      (node (ref "U1") (pin "95") (pinfunction "PTB16_._TSI0_CH9_._SPI1_SOUT_._UART0_RX_._I2S1_TXD0_._FB_AD17_._EWM_IN_._95") (pintype "bidirectional"))
    )
    (net (code "56") (name "/UART_TX") (class "Default")
      (node (ref "U1") (pin "96") (pinfunction "PTB17_._TSI0_CH10_._SPI1_SIN_._UART0_TX_._I2S1_TXD1_._FB_AD16_._EWM_OUT#_._96") (pintype "bidirectional"))
    )
    (net (code "57") (name "/USBCTRL") (class "Default")
      (node (ref "U1") (pin "119") (pinfunction "PTC14_._UART4_RX_._FB_AD25_._119") (pintype "bidirectional"))
    )
    (net (code "58") (name "/USBDN") (class "Default")
      (node (ref "U1") (pin "20") (pinfunction "USB0_DM_._20") (pintype "bidirectional"))
    )
    (net (code "59") (name "/USBDP") (class "Default")
      (node (ref "U1") (pin "19") (pinfunction "USB0_DP_._19") (pintype "bidirectional"))
    )
    (net (code "60") (name "/VFO") (class "Default")
      (node (ref "U1") (pin "84") (pinfunction "PTB3_._ADC0_SE13/TSI0_CH8_._I2C0_SDA_._UART0_CTS#/UART0_COL#_._ENET0_1588_TMR1_._FTM0_FLT0_._84") (pintype "bidirectional"))
    )
    (net (code "61") (name "/V_BUS") (class "Default")
      (node (ref "U1") (pin "45") (pinfunction "PTE24_._ADC0_SE17/EXTAL1_._CAN1_TX_._UART4_TX_._I2S1_TX_FS_._EWM_OUT#_._I2S1_RXD1_._45") (pintype "bidirectional"))
    )
    (net (code "62") (name "/V_U") (class "Default")
      (node (ref "U1") (pin "80") (pinfunction "PTA29_._ADC2_SE12_._ULPI_DATA7_._MII0_COL_._FB_A24_._80") (pintype "bidirectional"))
    )
    (net (code "63") (name "/V_V") (class "Default")
      (node (ref "U1") (pin "87") (pinfunction "PTB6_._ADC1_SE12_._FB_AD23_._87") (pintype "bidirectional"))
    )
    (net (code "64") (name "/V_W") (class "Default")
      (node (ref "U1") (pin "83") (pinfunction "PTB2_._ADC0_SE12/TSI0_CH7_._I2C0_SCL_._UART0_RTS#_._ENET0_1588_TMR0_._FTM0_FLT3_._83") (pintype "bidirectional"))
    )
    (net (code "65") (name "/XTAL") (class "Default")
      (node (ref "C26") (pin "1") (pinfunction "1_1") (pintype "passive"))
      (node (ref "R13") (pin "1") (pinfunction "1_1") (pintype "passive"))
      (node (ref "U1") (pin "73") (pinfunction "PTA19_._XTAL0_._FTM1_FLT0_._FTM_CLKIN1_._LPTMR0_ALT1_._73") (pintype "bidirectional"))
      (node (ref "Z2") (pin "1") (pinfunction "1_1") (pintype "passive"))
    )
    (net (code "66") (name "/ZCROSS") (class "Default")
      (node (ref "U1") (pin "60") (pinfunction "PTA8_._ADC0_SE11_._ULPI_NXT_._FTM1_CH0_._I2S1_RX_FS_._FTM1_QD_PHA_._TRACE_D2_._60") (pintype "bidirectional"))
    )
    (net (code "67") (name "AGND") (class "Default")
      (node (ref "C10") (pin "2") (pinfunction "2_2") (pintype "passive"))
      (node (ref "C5") (pin "2") (pinfunction "2_2") (pintype "passive"))
      (node (ref "C7") (pin "2") (pinfunction "2_2") (pintype "passive"))
      (node (ref "L3") (pin "1") (pinfunction "1_1") (pintype "passive"))
      (node (ref "L4") (pin "2") (pinfunction "2_2") (pintype "passive"))
      (node (ref "U1") (pin "34") (pinfunction "VSSA_._34") (pintype "power_in"))
    )
    (net (code "68") (name "DGND") (class "Default")
      (node (ref "B1") (pin "1") (pinfunction "1_1") (pintype "passive"))
      (node (ref "C1") (pin "2") (pinfunction "2_2") (pintype "passive"))
      (node (ref "C12") (pin "2") (pinfunction "2_2") (pintype "passive"))
      (node (ref "C13") (pin "1") (pinfunction "1_1") (pintype "passive"))
      (node (ref "C14") (pin "1") (pinfunction "1_1") (pintype "passive"))
      (node (ref "C15") (pin "1") (pinfunction "1_1") (pintype "passive"))
      (node (ref "C16") (pin "1") (pinfunction "1_1") (pintype "passive"))
      (node (ref "C17") (pin "1") (pinfunction "1_1") (pintype "passive"))
      (node (ref "C18") (pin "1") (pinfunction "1_1") (pintype "passive"))
      (node (ref "C19") (pin "1") (pinfunction "1_1") (pintype "passive"))
      (node (ref "C2") (pin "2") (pinfunction "2_2") (pintype "passive"))
      (node (ref "C20") (pin "1") (pinfunction "1_1") (pintype "passive"))
      (node (ref "C21") (pin "1") (pinfunction "1_1") (pintype "passive"))
      (node (ref "C22") (pin "2") (pinfunction "2_2") (pintype "passive"))
      (node (ref "C23") (pin "2") (pinfunction "2_2") (pintype "passive"))
      (node (ref "C24") (pin "2") (pinfunction "2_2") (pintype "passive"))
      (node (ref "C25") (pin "2") (pinfunction "2_2") (pintype "passive"))
      (node (ref "C26") (pin "2") (pinfunction "2_2") (pintype "passive"))
      (node (ref "C3") (pin "1") (pinfunction "1_1") (pintype "passive"))
      (node (ref "C4") (pin "2") (pinfunction "2_2") (pintype "passive"))
      (node (ref "C8") (pin "2") (pinfunction "2_2") (pintype "passive"))
      (node (ref "C9") (pin "2") (pinfunction "2_2") (pintype "passive"))
      (node (ref "J1") (pin "2") (pinfunction "2_2") (pintype "passive"))
      (node (ref "L4") (pin "1") (pinfunction "1_1") (pintype "passive"))
      (node (ref "Q1") (pin "2") (pinfunction "S_2") (pintype "passive"))
      (node (ref "R11") (pin "2") (pinfunction "2_2") (pintype "passive"))
      (node (ref "R8") (pin "2") (pinfunction "2_2") (pintype "passive"))
      (node (ref "SW1") (pin "5") (pinfunction "5_5") (pintype "passive"))
      (node (ref "SW1") (pin "6") (pinfunction "6_6") (pintype "passive"))
      (node (ref "SW1") (pin "7") (pinfunction "7_7") (pintype "passive"))
      (node (ref "SW1") (pin "8") (pinfunction "8_8") (pintype "passive"))
      (node (ref "U1") (pin "107") (pinfunction "VSS_._107") (pintype "power_in"))
      (node (ref "U1") (pin "121") (pinfunction "VSS_._121") (pintype "power_in"))
      (node (ref "U1") (pin "134") (pinfunction "VSS_._134") (pintype "power_in"))
      (node (ref "U1") (pin "17") (pinfunction "VSS_._17") (pintype "power_in"))
      (node (ref "U1") (pin "44") (pinfunction "VSS_._44") (pintype "power_in"))
      (node (ref "U1") (pin "57") (pinfunction "VSS_._57") (pintype "power_in"))
      (node (ref "U1") (pin "6") (pinfunction "VSS_._6") (pintype "power_in"))
      (node (ref "U1") (pin "71") (pinfunction "VSS_._71") (pintype "power_in"))
      (node (ref "U1") (pin "93") (pinfunction "VSS_._93") (pintype "power_in"))
      (node (ref "U2") (pin "7") (pinfunction "GND_7") (pintype "passive"))
      (node (ref "X1") (pin "1") (pinfunction "GND_1") (pintype "power_in"))
      (node (ref "X1") (pin "10") (pinfunction "GND_10") (pintype "power_in"))
      (node (ref "X2") (pin "10") (pinfunction "WP_10") (pintype "passive"))
      (node (ref "X2") (pin "11") (pinfunction "GND_11") (pintype "passive"))
      (node (ref "X2") (pin "12") (pinfunction "GND_12") (pintype "passive"))
      (node (ref "X2") (pin "6") (pinfunction "VSS2_6") (pintype "passive"))
      (node (ref "X2") (pin "9") (pintype "passive"))
    )
    (net (code "69") (name "Net-(B1-Pad2)") (class "Default")
      (node (ref "B1") (pin "2") (pinfunction "2_2") (pintype "passive"))
      (node (ref "R1") (pin "2") (pinfunction "2_2") (pintype "passive"))
    )
    (net (code "70") (name "Net-(C7-Pad1)") (class "Default")
      (node (ref "C7") (pin "1") (pinfunction "1_1") (pintype "passive"))
      (node (ref "R10") (pin "1") (pinfunction "1_1") (pintype "passive"))
    )
    (net (code "71") (name "Net-(D2-Pad1)") (class "Default")
      (node (ref "D2") (pin "1") (pinfunction "1_1") (pintype "passive"))
      (node (ref "R16") (pin "2") (pinfunction "2_2") (pintype "passive"))
    )
    (net (code "72") (name "Net-(D3-Pad1)") (class "Default")
      (node (ref "D3") (pin "1") (pinfunction "1_1") (pintype "passive"))
      (node (ref "R17") (pin "2") (pinfunction "2_2") (pintype "passive"))
    )
    (net (code "73") (name "Net-(D4-Pad1)") (class "Default")
      (node (ref "D4") (pin "1") (pinfunction "1_1") (pintype "passive"))
      (node (ref "R18") (pin "2") (pinfunction "2_2") (pintype "passive"))
    )
    (net (code "74") (name "Net-(Q1-D)") (class "Default")
      (node (ref "BZ1") (pin "2") (pinfunction "2_2") (pintype "passive"))
      (node (ref "Q1") (pin "3") (pinfunction "D_3") (pintype "passive"))
      (node (ref "VD1") (pin "A") (pinfunction "A_A") (pintype "passive"))
    )
    (net (code "75") (name "Net-(U1-DAC0_OUT{slash}CMP1_IN3{slash}ADC0_SE23_.)") (class "Default")
      (node (ref "TP8") (pin "1") (pinfunction "1_1") (pintype "passive"))
      (node (ref "U1") (pin "38") (pinfunction "DAC0_OUT/CMP1_IN3/ADC0_SE23_._38") (pintype "bidirectional"))
    )
    (net (code "76") (name "Net-(U1-DAC1_OUT{slash}CMP0_IN4{slash}CMP2_IN3{slash}ADC1_SE23_.)") (class "Default")
      (node (ref "TP9") (pin "1") (pinfunction "1_1") (pintype "passive"))
      (node (ref "U1") (pin "39") (pinfunction "DAC1_OUT/CMP0_IN4/CMP2_IN3/ADC1_SE23_._39") (pintype "bidirectional"))
    )
    (net (code "77") (name "Net-(U1-EXTAL32_.)") (class "Default")
      (node (ref "C9") (pin "1") (pinfunction "1_1") (pintype "passive"))
      (node (ref "U1") (pin "41") (pinfunction "EXTAL32_._41") (pintype "bidirectional"))
      (node (ref "Z1") (pin "4") (pinfunction "4_4") (pintype "passive"))
    )
    (net (code "78") (name "Net-(U1-PGA2_DM{slash}ADC2_DM0{slash}ADC3_DM3{slash}ADC0_DM1_.)") (class "Default")
      (node (ref "TP14") (pin "1") (pinfunction "1_1") (pintype "passive"))
      (node (ref "U1") (pin "24") (pinfunction "PGA2_DM/ADC2_DM0/ADC3_DM3/ADC0_DM1_._24") (pintype "bidirectional"))
    )
    (net (code "79") (name "Net-(U1-PGA2_DP{slash}ADC2_DP0{slash}ADC3_DP3{slash}ADC0_DP1_.)") (class "Default")
      (node (ref "TP13") (pin "1") (pinfunction "1_1") (pintype "passive"))
      (node (ref "U1") (pin "23") (pinfunction "PGA2_DP/ADC2_DP0/ADC3_DP3/ADC0_DP1_._23") (pintype "bidirectional"))
    )
    (net (code "80") (name "Net-(U1-PGA3_DM{slash}ADC3_DM0{slash}ADC2_DM3{slash}ADC1_DM1_.)") (class "Default")
      (node (ref "TP16") (pin "1") (pinfunction "1_1") (pintype "passive"))
      (node (ref "U1") (pin "26") (pinfunction "PGA3_DM/ADC3_DM0/ADC2_DM3/ADC1_DM1_._26") (pintype "bidirectional"))
    )
    (net (code "81") (name "Net-(U1-PGA3_DP{slash}ADC3_DP0{slash}ADC2_DP3{slash}ADC1_DP1_.)") (class "Default")
      (node (ref "TP15") (pin "1") (pinfunction "1_1") (pintype "passive"))
      (node (ref "U1") (pin "25") (pinfunction "PGA3_DP/ADC3_DP0/ADC2_DP3/ADC1_DP1_._25") (pintype "bidirectional"))
    )
    (net (code "82") (name "Net-(U1-PTA24_._CMP3_IN4_._ULPI_DATA2_._MII0_TXD2_._FB_A29_.)") (class "Default")
      (node (ref "D2") (pin "2") (pinfunction "2_2") (pintype "passive"))
      (node (ref "U1") (pin "75") (pinfunction "PTA24_._CMP3_IN4_._ULPI_DATA2_._MII0_TXD2_._FB_A29_._75") (pintype "bidirectional"))
    )
    (net (code "83") (name "Net-(U1-PTA25_._CMP3_IN5_._ULPI_DATA3_._MII0_TXCLK_._FB_A28_.)") (class "Default")
      (node (ref "D3") (pin "2") (pinfunction "2_2") (pintype "passive"))
      (node (ref "U1") (pin "76") (pinfunction "PTA25_._CMP3_IN5_._ULPI_DATA3_._MII0_TXCLK_._FB_A28_._76") (pintype "bidirectional"))
    )
    (net (code "84") (name "Net-(U1-PTA26_._ADC2_SE15_._ULPI_DATA4_._MII0_TXD3_._FB_A27_.)") (class "Default")
      (node (ref "D4") (pin "2") (pinfunction "2_2") (pintype "passive"))
      (node (ref "U1") (pin "77") (pinfunction "PTA26_._ADC2_SE15_._ULPI_DATA4_._MII0_TXD3_._FB_A27_._77") (pintype "bidirectional"))
    )
    (net (code "85") (name "Net-(U1-PTC5{slash}LLWU_P9_._SPI0_SCK_._LPTMR0_ALT2_._I2S0_RXD0_._FB_AD10{slash}NFC_DATA7_._CMP0_OUT_._I2S1_TX_FS_.)") (class "Default")
      (node (ref "TP1") (pin "1") (pinfunction "1_1") (pintype "passive"))
      (node (ref "U1") (pin "110") (pinfunction "PTC5/LLWU_P9_._SPI0_SCK_._LPTMR0_ALT2_._I2S0_RXD0_._FB_AD10/NFC_DATA7_._CMP0_OUT_._I2S1_TX_FS_._110") (pintype "bidirectional"))
    )
    (net (code "86") (name "Net-(U1-PTC6{slash}LLWU_P10_._CMP0_IN0_._SPI0_SOUT_._PDB0_EXTRG_._I2S0_RX#CLK_._FB_AD9{slash}NFC_DATA6_._I2S0_MCLK_.)") (class "Default")
      (node (ref "TP2") (pin "1") (pinfunction "1_1") (pintype "passive"))
      (node (ref "U1") (pin "111") (pinfunction "PTC6/LLWU_P10_._CMP0_IN0_._SPI0_SOUT_._PDB0_EXTRG_._I2S0_RX#CLK_._FB_AD9/NFC_DATA6_._I2S0_MCLK_._111") (pintype "bidirectional"))
    )
    (net (code "87") (name "Net-(U1-PTC7_._CMP0_IN1_._SPI0_SIN_._USB_SOF_OUT_._I2S0_RX_FS_._FB_AD8{slash}NFC_DATA5_.)") (class "Default")
      (node (ref "TP3") (pin "1") (pinfunction "1_1") (pintype "passive"))
      (node (ref "U1") (pin "112") (pinfunction "PTC7_._CMP0_IN1_._SPI0_SIN_._USB_SOF_OUT_._I2S0_RX_FS_._FB_AD8/NFC_DATA5_._112") (pintype "bidirectional"))
    )
    (net (code "88") (name "Net-(U1-PTC8_._ADC1_SE4b{slash}CMP0_IN2_._FTM3_CH4_._I2S0_MCLK_._FB_AD7{slash}NFC_DATA4_.)") (class "Default")
      (node (ref "TP4") (pin "1") (pinfunction "1_1") (pintype "passive"))
      (node (ref "U1") (pin "113") (pinfunction "PTC8_._ADC1_SE4b/CMP0_IN2_._FTM3_CH4_._I2S0_MCLK_._FB_AD7/NFC_DATA4_._113") (pintype "bidirectional"))
    )
    (net (code "89") (name "Net-(U1-PTC9_._ADC1_SE5b{slash}CMP0_IN3_._FTM3_CH5_._I2S0_RX#CLK_._FB_AD6{slash}NFC_DATA3_._FTM2_FLT0_.)") (class "Default")
      (node (ref "TP5") (pin "1") (pinfunction "1_1") (pintype "passive"))
      (node (ref "U1") (pin "114") (pinfunction "PTC9_._ADC1_SE5b/CMP0_IN3_._FTM3_CH5_._I2S0_RX#CLK_._FB_AD6/NFC_DATA3_._FTM2_FLT0_._114") (pintype "bidirectional"))
    )
    (net (code "90") (name "Net-(U1-PTC10_._ADC1_SE6b_._I2C1_SCL_._FTM3_CH6_._I2S0_RX_FS_._FB_AD5{slash}NFC_DATA2_._I2S1_MCLK_.)") (class "Default")
      (node (ref "TP6") (pin "1") (pinfunction "1_1") (pintype "passive"))
      (node (ref "U1") (pin "115") (pinfunction "PTC10_._ADC1_SE6b_._I2C1_SCL_._FTM3_CH6_._I2S0_RX_FS_._FB_AD5/NFC_DATA2_._I2S1_MCLK_._115") (pintype "bidirectional"))
    )
    (net (code "91") (name "Net-(U1-PTC11{slash}LLWU_P11_._ADC1_SE7b_._I2C1_SDA_._FTM3_CH7_._I2S0_RXD1_._FB_RW#{slash}NFC_WE_.)") (class "Default")
      (node (ref "TP7") (pin "1") (pinfunction "1_1") (pintype "passive"))
      (node (ref "U1") (pin "116") (pinfunction "PTC11/LLWU_P11_._ADC1_SE7b_._I2C1_SDA_._FTM3_CH7_._I2S0_RXD1_._FB_RW#/NFC_WE_._116") (pintype "bidirectional"))
    )
    (net (code "92") (name "Net-(U1-PTC16_._CAN1_RX_._UART3_RX_._ENET0_1588_TMR0_._FB_CS5#{slash}FB_TSIZ1{slash}FB#E23_16#_._NFC_RB_.)") (class "Default")
      (node (ref "SW1") (pin "1") (pinfunction "1_1") (pintype "passive"))
      (node (ref "U1") (pin "123") (pinfunction "PTC16_._CAN1_RX_._UART3_RX_._ENET0_1588_TMR0_._FB_CS5#/FB_TSIZ1/FB#E23_16#_._NFC_RB_._123") (pintype "bidirectional"))
    )
    (net (code "93") (name "Net-(U1-PTC17_._CAN1_TX_._UART3_TX_._ENET0_1588_TMR1_._FB_CS4#{slash}FB_TSIZ0{slash}FB#E31_24#_._NFC_CE0#_.)") (class "Default")
      (node (ref "SW1") (pin "2") (pinfunction "2_2") (pintype "passive"))
      (node (ref "U1") (pin "124") (pinfunction "PTC17_._CAN1_TX_._UART3_TX_._ENET0_1588_TMR1_._FB_CS4#/FB_TSIZ0/FB#E31_24#_._NFC_CE0#_._124") (pintype "bidirectional"))
    )
    (net (code "94") (name "Net-(U1-PTC18_._UART3_RTS#_._ENET0_1588_TMR2_._FB_TBST#{slash}FB_CS2#{slash}FB#E15_8#_._NFC_CE1#_.)") (class "Default")
      (node (ref "SW1") (pin "3") (pinfunction "3_3") (pintype "passive"))
      (node (ref "U1") (pin "125") (pinfunction "PTC18_._UART3_RTS#_._ENET0_1588_TMR2_._FB_TBST#/FB_CS2#/FB#E15_8#_._NFC_CE1#_._125") (pintype "bidirectional"))
    )
    (net (code "95") (name "Net-(U1-PTC19_._UART3_CTS#_._ENET0_1588_TMR3_._FB_CS3#{slash}FB#E7_0#_._FB_TA#_.)") (class "Default")
      (node (ref "SW1") (pin "4") (pinfunction "4_4") (pintype "passive"))
      (node (ref "U1") (pin "126") (pinfunction "PTC19_._UART3_CTS#_._ENET0_1588_TMR3_._FB_CS3#/FB#E7_0#_._FB_TA#_._126") (pintype "bidirectional"))
    )
    (net (code "96") (name "Net-(U1-PTD0{slash}LLWU_P12_._SPI0_PCS0_._UART2_RTS#_._FTM3_CH0_._FB_ALE{slash}FB_CS1#{slash}FB_TS#_._I2S1_RXD1_.)") (class "Default")
      (node (ref "TP10") (pin "1") (pinfunction "1_1") (pintype "passive"))
      (node (ref "U1") (pin "127") (pinfunction "PTD0/LLWU_P12_._SPI0_PCS0_._UART2_RTS#_._FTM3_CH0_._FB_ALE/FB_CS1#/FB_TS#_._I2S1_RXD1_._127") (pintype "bidirectional"))
    )
    (net (code "97") (name "Net-(U1-PTD1_._ADC0_SE5b_._SPI0_SCK_._UART2_CTS#_._FTM3_CH1_._FB_CS0#_._I2S1_RXD0_.)") (class "Default")
      (node (ref "TP11") (pin "1") (pinfunction "1_1") (pintype "passive"))
      (node (ref "U1") (pin "128") (pinfunction "PTD1_._ADC0_SE5b_._SPI0_SCK_._UART2_CTS#_._FTM3_CH1_._FB_CS0#_._I2S1_RXD0_._128") (pintype "bidirectional"))
    )
    (net (code "98") (name "Net-(U1-PTD2{slash}LLWU_P13_._SPI0_SOUT_._UART2_RX_._FTM3_CH2_._FB_AD4_._I2S1_RX_FS_.)") (class "Default")
      (node (ref "TP12") (pin "1") (pinfunction "1_1") (pintype "passive"))
      (node (ref "U1") (pin "129") (pinfunction "PTD2/LLWU_P13_._SPI0_SOUT_._UART2_RX_._FTM3_CH2_._FB_AD4_._I2S1_RX_FS_._129") (pintype "bidirectional"))
    )
    (net (code "99") (name "Net-(U1-VBAT_.)") (class "Default")
      (node (ref "D1") (pin "3") (pintype "passive"))
      (node (ref "R1") (pin "1") (pinfunction "1_1") (pintype "passive"))
      (node (ref "U1") (pin "42") (pinfunction "VBAT_._42") (pintype "power_in"))
    )
    (net (code "100") (name "Net-(U1-VDDA_.)") (class "Default")
      (node (ref "C10") (pin "1") (pinfunction "1_1") (pintype "passive"))
      (node (ref "C5") (pin "1") (pinfunction "1_1") (pintype "passive"))
      (node (ref "L1") (pin "2") (pinfunction "2_2") (pintype "passive"))
      (node (ref "L2") (pin "1") (pinfunction "1_1") (pintype "passive"))
      (node (ref "U1") (pin "31") (pinfunction "VDDA_._31") (pintype "power_in"))
    )
    (net (code "101") (name "Net-(U1-VOUT33_.)") (class "Default")
      (node (ref "C12") (pin "1") (pinfunction "1_1") (pintype "passive"))
      (node (ref "R6") (pin "1") (pinfunction "1_1") (pintype "passive"))
      (node (ref "U1") (pin "21") (pinfunction "VOUT33_._21") (pintype "bidirectional"))
    )
    (net (code "102") (name "Net-(U1-VREFH_.)") (class "Default")
      (node (ref "C11") (pin "2") (pinfunction "2_2") (pintype "passive"))
      (node (ref "C6") (pin "2") (pinfunction "2_2") (pintype "passive"))
      (node (ref "L2") (pin "2") (pinfunction "2_2") (pintype "passive"))
      (node (ref "U1") (pin "32") (pinfunction "VREFH_._32") (pintype "power_in"))
    )
    (net (code "103") (name "Net-(U1-VREFL_.)") (class "Default")
      (node (ref "C11") (pin "1") (pinfunction "1_1") (pintype "passive"))
      (node (ref "C6") (pin "1") (pinfunction "1_1") (pintype "passive"))
      (node (ref "L3") (pin "2") (pinfunction "2_2") (pintype "passive"))
      (node (ref "U1") (pin "33") (pinfunction "VREFL_._33") (pintype "power_in"))
    )
    (net (code "104") (name "Net-(U1-VREF_OUT{slash}CMP1_IN5{slash}CMP0_IN5{slash}ADC1_SE18_.)") (class "Default")
      (node (ref "R10") (pin "2") (pinfunction "2_2") (pintype "passive"))
      (node (ref "U1") (pin "37") (pinfunction "VREF_OUT/CMP1_IN5/CMP0_IN5/ADC1_SE18_._37") (pintype "bidirectional"))
    )
    (net (code "105") (name "Net-(U1-VREGIN_.)") (class "Default")
      (node (ref "R12") (pin "1") (pinfunction "1_1") (pintype "passive"))
      (node (ref "U1") (pin "22") (pinfunction "VREGIN_._22") (pintype "input"))
    )
    (net (code "106") (name "Net-(U1-XTAL32_.)") (class "Default")
      (node (ref "C8") (pin "1") (pinfunction "1_1") (pintype "passive"))
      (node (ref "U1") (pin "40") (pinfunction "XTAL32_._40") (pintype "bidirectional"))
      (node (ref "Z1") (pin "1") (pinfunction "1_1") (pintype "passive"))
    )
    (net (code "107") (name "Net-(X1-RTCK)") (class "Default")
      (node (ref "R8") (pin "1") (pinfunction "1_1") (pintype "passive"))
      (node (ref "X1") (pin "6") (pinfunction "RTCK_6") (pintype "input"))
    )
    (net (code "108") (name "Net-(X1-TDO)") (class "Default")
      (node (ref "R3") (pin "2") (pinfunction "2_2") (pintype "passive"))
      (node (ref "X1") (pin "7") (pinfunction "TDO_7") (pintype "output"))
    )
    (net (code "109") (name "V5V") (class "Default")
      (node (ref "BZ1") (pin "1") (pinfunction "1_1") (pintype "passive"))
      (node (ref "C3") (pin "2") (pinfunction "2_2") (pintype "passive"))
      (node (ref "R12") (pin "2") (pinfunction "2_2") (pintype "passive"))
      (node (ref "VD1") (pin "K") (pinfunction "K_K") (pintype "passive"))
    )
    (net (code "110") (name "VDDC") (class "Default")
      (node (ref "C1") (pin "1") (pinfunction "1_1") (pintype "passive"))
      (node (ref "C13") (pin "2") (pinfunction "2_2") (pintype "passive"))
      (node (ref "C14") (pin "2") (pinfunction "2_2") (pintype "passive"))
      (node (ref "C15") (pin "2") (pinfunction "2_2") (pintype "passive"))
      (node (ref "C16") (pin "2") (pinfunction "2_2") (pintype "passive"))
      (node (ref "C17") (pin "2") (pinfunction "2_2") (pintype "passive"))
      (node (ref "C18") (pin "2") (pinfunction "2_2") (pintype "passive"))
      (node (ref "C19") (pin "2") (pinfunction "2_2") (pintype "passive"))
      (node (ref "C2") (pin "1") (pinfunction "1_1") (pintype "passive"))
      (node (ref "C20") (pin "2") (pinfunction "2_2") (pintype "passive"))
      (node (ref "C21") (pin "2") (pinfunction "2_2") (pintype "passive"))
      (node (ref "C22") (pin "1") (pinfunction "1_1") (pintype "passive"))
      (node (ref "C23") (pin "1") (pinfunction "1_1") (pintype "passive"))
      (node (ref "C24") (pin "1") (pinfunction "1_1") (pintype "passive"))
      (node (ref "D1") (pin "2") (pintype "passive"))
      (node (ref "L1") (pin "1") (pinfunction "1_1") (pintype "passive"))
      (node (ref "R14") (pin "1") (pinfunction "1_1") (pintype "passive"))
      (node (ref "R15") (pin "1") (pinfunction "1_1") (pintype "passive"))
      (node (ref "R16") (pin "1") (pinfunction "1_1") (pintype "passive"))
      (node (ref "R17") (pin "1") (pinfunction "1_1") (pintype "passive"))
      (node (ref "R18") (pin "1") (pinfunction "1_1") (pintype "passive"))
      (node (ref "R2") (pin "1") (pinfunction "1_1") (pintype "passive"))
      (node (ref "R4") (pin "1") (pinfunction "1_1") (pintype "passive"))
      (node (ref "R5") (pin "1") (pinfunction "1_1") (pintype "passive"))
      (node (ref "R6") (pin "2") (pinfunction "2_2") (pintype "passive"))
      (node (ref "R7") (pin "1") (pinfunction "1_1") (pintype "passive"))
      (node (ref "R9") (pin "1") (pinfunction "1_1") (pintype "passive"))
      (node (ref "U1") (pin "108") (pinfunction "VDD_._108") (pintype "power_in"))
      (node (ref "U1") (pin "122") (pinfunction "VDD_._122") (pintype "power_in"))
      (node (ref "U1") (pin "135") (pinfunction "VDD_._135") (pintype "power_in"))
      (node (ref "U1") (pin "16") (pinfunction "VDD_._16") (pintype "power_in"))
      (node (ref "U1") (pin "43") (pinfunction "VDD_._43") (pintype "power_in"))
      (node (ref "U1") (pin "5") (pinfunction "VDD_._5") (pintype "power_in"))
      (node (ref "U1") (pin "56") (pinfunction "VDD_._56") (pintype "power_in"))
      (node (ref "U1") (pin "70") (pinfunction "VDD_._70") (pintype "power_in"))
      (node (ref "U1") (pin "94") (pinfunction "VDD_._94") (pintype "power_in"))
      (node (ref "U2") (pin "5") (pinfunction "~{WP}_5") (pintype "passive"))
      (node (ref "U2") (pin "6") (pinfunction "VCC_6") (pintype "passive"))
      (node (ref "X1") (pin "9") (pinfunction "VCC_9") (pintype "power_in"))
      (node (ref "X2") (pin "4") (pinfunction "VDD_4") (pintype "passive"))
    )
    (net (code "111") (name "unconnected-(D1-Pad1)") (class "Default")
      (node (ref "D1") (pin "1") (pintype "passive"))
    )
    (net (code "112") (name "unconnected-(U1-PGA1_DM{slash}ADC1_DM0{slash}ADC0_DM3_.-Pad30)") (class "Default")
      (node (ref "U1") (pin "30") (pinfunction "PGA1_DM/ADC1_DM0/ADC0_DM3_._30") (pintype "bidirectional"))
    )
    (net (code "113") (name "unconnected-(U1-PGA1_DP{slash}ADC1_DP0{slash}ADC0_DP3_.-Pad29)") (class "Default")
      (node (ref "U1") (pin "29") (pinfunction "PGA1_DP/ADC1_DP0/ADC0_DP3_._29") (pintype "bidirectional"))
    )
    (net (code "114") (name "unconnected-(U1-PTA4{slash}LLWU_P3_._TSI0_CH5_._FTM0_CH1_._NMI#_._EZP_CS#-Pad54)") (class "Default")
      (node (ref "U1") (pin "54") (pinfunction "PTA4/LLWU_P3_._TSI0_CH5_._FTM0_CH1_._NMI#_._EZP_CS#_54") (pintype "bidirectional"))
    )
    (net (code "115") (name "unconnected-(U1-PTA6_._ADC3_SE6a_._ULPI_CLK_._FTM0_CH3_._I2S1_RXD0_._CLKOUT_._TRACE_CLKOUT_.-Pad58)") (class "Default")
      (node (ref "U1") (pin "58") (pinfunction "PTA6_._ADC3_SE6a_._ULPI_CLK_._FTM0_CH3_._I2S1_RXD0_._CLKOUT_._TRACE_CLKOUT_._58") (pintype "bidirectional"))
    )
    (net (code "116") (name "unconnected-(U1-PTA7_._ADC0_SE10_._ULPI_DIR_._FTM0_CH4_._I2S1_RX#CLK_._TRACE_D3_.-Pad59)") (class "Default")
      (node (ref "U1") (pin "59") (pinfunction "PTA7_._ADC0_SE10_._ULPI_DIR_._FTM0_CH4_._I2S1_RX#CLK_._TRACE_D3_._59") (pintype "bidirectional"))
    )
    (net (code "117") (name "unconnected-(U1-PTA9_._ADC3_SE5a_._ULPI_STP_._FTM1_CH1_._MII0_RXD3_._FTM1_QD_PHB_._TRACE_D1_.-Pad61)") (class "Default")
      (node (ref "U1") (pin "61") (pinfunction "PTA9_._ADC3_SE5a_._ULPI_STP_._FTM1_CH1_._MII0_RXD3_._FTM1_QD_PHB_._TRACE_D1_._61") (pintype "bidirectional"))
    )
    (net (code "118") (name "unconnected-(U1-PTA27_._ADC2_SE14_._ULPI_DATA5_._MII0_CRS_._FB_A26_.-Pad78)") (class "Default")
      (node (ref "U1") (pin "78") (pinfunction "PTA27_._ADC2_SE14_._ULPI_DATA5_._MII0_CRS_._FB_A26_._78") (pintype "bidirectional"))
    )
    (net (code "119") (name "unconnected-(U1-PTA28_._ADC2_SE13_._ULPI_DATA6_._MII0_TXER_._FB_A25_.-Pad79)") (class "Default")
      (node (ref "U1") (pin "79") (pinfunction "PTA28_._ADC2_SE13_._ULPI_DATA6_._MII0_TXER_._FB_A25_._79") (pintype "bidirectional"))
    )
    (net (code "120") (name "unconnected-(U1-PTB0{slash}LLWU_P5_._ADC0-3_SE8{slash}TSI0_CH0_._I2C0_SCL_._FTM1_CH0_._RMII0_MDIO{slash}MII0_MDIO_._FTM1_QD_PHA_.-Pad81)") (class "Default")
      (node (ref "U1") (pin "81") (pinfunction "PTB0/LLWU_P5_._ADC0-3_SE8/TSI0_CH0_._I2C0_SCL_._FTM1_CH0_._RMII0_MDIO/MII0_MDIO_._FTM1_QD_PHA_._81") (pintype "bidirectional"))
    )
    (net (code "121") (name "unconnected-(U1-PTB1_._ADC0-3_SE9{slash}TSI0_CH6_._I2C0_SDA_._FTM1_CH1_._RMII0_MDC{slash}MII0_MDC_._FTM1_QD_PHB_.-Pad82)") (class "Default")
      (node (ref "U1") (pin "82") (pinfunction "PTB1_._ADC0-3_SE9/TSI0_CH6_._I2C0_SDA_._FTM1_CH1_._RMII0_MDC/MII0_MDC_._FTM1_QD_PHB_._82") (pintype "bidirectional"))
    )
    (net (code "122") (name "unconnected-(U1-PTB4_._ADC1_SE10_._ENET0_1588_TMR2_._FTM1_FLT0_.-Pad85)") (class "Default")
      (node (ref "U1") (pin "85") (pinfunction "PTB4_._ADC1_SE10_._ENET0_1588_TMR2_._FTM1_FLT0_._85") (pintype "bidirectional"))
    )
    (net (code "123") (name "unconnected-(U1-PTB5_._ADC1_SE11_._ENET0_1588_TMR3_._FTM2_FLT0_.-Pad86)") (class "Default")
      (node (ref "U1") (pin "86") (pinfunction "PTB5_._ADC1_SE11_._ENET0_1588_TMR3_._FTM2_FLT0_._86") (pintype "bidirectional"))
    )
    (net (code "124") (name "unconnected-(U1-PTB7_._ADC1_SE13_._FB_AD22_.-Pad88)") (class "Default")
      (node (ref "U1") (pin "88") (pinfunction "PTB7_._ADC1_SE13_._FB_AD22_._88") (pintype "bidirectional"))
    )
    (net (code "125") (name "unconnected-(U1-PTB8_._UART3_RTS#_._FB_AD21_.-Pad89)") (class "Default")
      (node (ref "U1") (pin "89") (pinfunction "PTB8_._UART3_RTS#_._FB_AD21_._89") (pintype "bidirectional"))
    )
    (net (code "126") (name "unconnected-(U1-PTB9_._SPI1_PCS1_._UART3_CTS#_._FB_AD20_.-Pad90)") (class "Default")
      (node (ref "U1") (pin "90") (pinfunction "PTB9_._SPI1_PCS1_._UART3_CTS#_._FB_AD20_._90") (pintype "bidirectional"))
    )
    (net (code "127") (name "unconnected-(U1-PTB11_._ADC1_SE15_._SPI1_SCK_._UART3_TX_._I2S1_TX_FS_._FB_AD18_._FTM0_FLT2_.-Pad92)") (class "Default")
      (node (ref "U1") (pin "92") (pinfunction "PTB11_._ADC1_SE15_._SPI1_SCK_._UART3_TX_._I2S1_TX_FS_._FB_AD18_._FTM0_FLT2_._92") (pintype "bidirectional"))
    )
    (net (code "128") (name "unconnected-(U1-PTC15_._UART4_TX_._FB_AD24_.-Pad120)") (class "Default")
      (node (ref "U1") (pin "120") (pinfunction "PTC15_._UART4_TX_._FB_AD24_._120") (pintype "bidirectional"))
    )
    (net (code "129") (name "unconnected-(U1-PTD3_._SPI0_SIN_._UART2_TX_._FTM3_CH3_._FB_AD3_._I2S1_RX#CLK_.-Pad130)") (class "Default")
      (node (ref "U1") (pin "130") (pinfunction "PTD3_._SPI0_SIN_._UART2_TX_._FTM3_CH3_._FB_AD3_._I2S1_RX#CLK_._130") (pintype "bidirectional"))
    )
    (net (code "130") (name "unconnected-(U1-PTD7_._CMT_IRO_._UART0_TX_._FTM0_CH7_._FTM0_FLT1_.-Pad136)") (class "Default")
      (node (ref "U1") (pin "136") (pinfunction "PTD7_._CMT_IRO_._UART0_TX_._FTM0_CH7_._FTM0_FLT1_._136") (pintype "bidirectional"))
    )
    (net (code "131") (name "unconnected-(U1-PTD10_._UART5_RTS#_._FB_A18{slash}NFC_RE_.-Pad139)") (class "Default")
      (node (ref "U1") (pin "139") (pinfunction "PTD10_._UART5_RTS#_._FB_A18/NFC_RE_._139") (pintype "bidirectional"))
    )
    (net (code "132") (name "unconnected-(U1-PTE9_._ADC2_SE17_._I2S0_TXD1_._UART5_RX_._I2S0_RX#CLK_._FTM3_CH4_.-Pad12)") (class "Default")
      (node (ref "U1") (pin "12") (pinfunction "PTE9_._ADC2_SE17_._I2S0_TXD1_._UART5_RX_._I2S0_RX#CLK_._FTM3_CH4_._12") (pintype "bidirectional"))
    )
    (net (code "133") (name "unconnected-(U1-PTE10_._UART5_CTS#_._I2S0_TXD0_._FTM3_CH5_.-Pad13)") (class "Default")
      (node (ref "U1") (pin "13") (pinfunction "PTE10_._UART5_CTS#_._I2S0_TXD0_._FTM3_CH5_._13") (pintype "bidirectional"))
    )
    (net (code "134") (name "unconnected-(U1-PTE11_._ADC3_SE16_._UART5_RTS#_._I2S0_TX_FS_._FTM3_CH6_.-Pad14)") (class "Default")
      (node (ref "U1") (pin "14") (pinfunction "PTE11_._ADC3_SE16_._UART5_RTS#_._I2S0_TX_FS_._FTM3_CH6_._14") (pintype "bidirectional"))
    )
    (net (code "135") (name "unconnected-(U1-PTE12_._ADC3_SE17_._I2S0_TX#CLK_._FTM3_CH7_.-Pad15)") (class "Default")
      (node (ref "U1") (pin "15") (pinfunction "PTE12_._ADC3_SE17_._I2S0_TX#CLK_._FTM3_CH7_._15") (pintype "bidirectional"))
    )
    (net (code "136") (name "unconnected-(U1-PTE25_._ADC0_SE18{slash}XTAL1_._CAN1_RX_._UART4_RX_._I2S1_TX#CLK_._EWM_IN_._I2S1_TXD1_.-Pad46)") (class "Default")
      (node (ref "U1") (pin "46") (pinfunction "PTE25_._ADC0_SE18/XTAL1_._CAN1_RX_._UART4_RX_._I2S1_TX#CLK_._EWM_IN_._I2S1_TXD1_._46") (pintype "bidirectional"))
    )
    (net (code "137") (name "unconnected-(U1-PTE27_._ADC3_SE4b_._UART4_RTS#_._I2S1_MCLK_.-Pad48)") (class "Default")
      (node (ref "U1") (pin "48") (pinfunction "PTE27_._ADC3_SE4b_._UART4_RTS#_._I2S1_MCLK_._48") (pintype "bidirectional"))
    )
    (net (code "138") (name "unconnected-(U1-VSS_.-Pad18)") (class "Default")
      (node (ref "U1") (pin "18") (pinfunction "VSS_._18") (pintype "power_in"))
    )
  )
)
